# ProximityDetector.net
KiCad netlist of a schematic drawn in Altium Designer
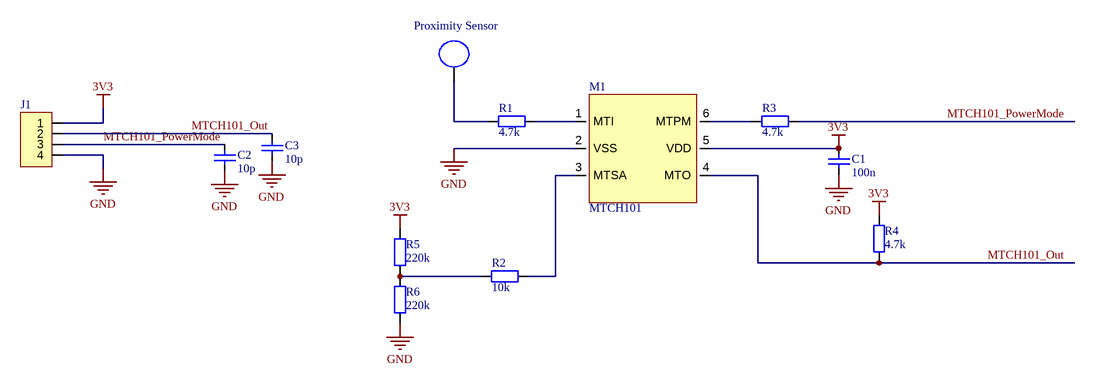
[diagram p0: ProximityDetector.SchDoc]

(export (version "E")
  (design (tool "Eeschema 10.0.6"))
  (components
    (comp (ref "C1")
      (value "100n")
      (footprint "0805_C")
      (description "Cap")
      (libsource (lib "Sch_Lib") (part "Cap"))
    )
    (comp (ref "C2")
      (value "10p")
      (footprint "0805_C")
      (description "Cap")
      (libsource (lib "Sch_Lib") (part "Cap"))
    )
    (comp (ref "C3")
      (value "10p")
      (footprint "0805_C")
      (description "Cap")
      (libsource (lib "Sch_Lib") (part "Cap"))
    )
    (comp (ref "J1") (value "~") (footprint "CON_THT_4P_RM2.54") (libsource (lib "Sch_Lib") (part "CON_4P")))
    (comp (ref "M1")
      (value "MTCH101")
      (footprint "SOT23-6")
      (libsource (lib "ProximityDetector") (part "MTCH101"))
    )
    (comp (ref "Proximity Sensor")
      (value "Detector")
      (footprint "Hole_1.3mm")
      (libsource (lib "ProximityDetector_1") (part "Detector"))
    )
    (comp (ref "R1")
      (value "4.7k")
      (footprint "0805_R")
      (description "Res")
      (libsource (lib "Sch_Lib") (part "Res"))
    )
    (comp (ref "R2")
      (value "10k")
      (footprint "0805_R")
      (description "Res")
      (libsource (lib "Sch_Lib") (part "Res"))
    )
    (comp (ref "R3")
      (value "4.7k")
      (footprint "0805_R")
      (description "Res")
      (libsource (lib "Sch_Lib") (part "Res"))
    )
    (comp (ref "R4")
      (value "4.7k")
      (footprint "0805_R")
      (description "Res")
      (libsource (lib "") (part "Res_1"))
    )
    (comp (ref "R5")
      (value "220k")
      (footprint "0805_R")
      (description "Res")
      (libsource (lib "") (part "Res_1"))
    )
    (comp (ref "R6")
      (value "220k")
      (footprint "0805_R")
      (description "Res")
      (libsource (lib "") (part "Res_1"))
    )
  )
  (nets
    (net (code "1") (name "/MTCH101_Out") (class "Default")
      (node (ref "C3") (pin "2") (pinfunction "2_2") (pintype "passive"))
      (node (ref "J1") (pin "2") (pinfunction "2_2") (pintype "passive"))
      (node (ref "M1") (pin "4") (pinfunction "MTO_4") (pintype "passive"))
      (node (ref "R4") (pin "1") (pinfunction "1_1") (pintype "passive"))
    )
    (net (code "2") (name "/MTCH101_PowerMode") (class "Default")
      (node (ref "C2") (pin "2") (pinfunction "2_2") (pintype "passive"))
      (node (ref "J1") (pin "3") (pinfunction "3_3") (pintype "passive"))
      (node (ref "R3") (pin "2") (pinfunction "2_2") (pintype "passive"))
    )
    (net (code "3") (name "3V3") (class "Default")
      (node (ref "C1") (pin "2") (pinfunction "2_2") (pintype "passive"))
      (node (ref "J1") (pin "1") (pinfunction "1_1") (pintype "passive"))
      (node (ref "M1") (pin "5") (pinfunction "VDD_5") (pintype "passive"))
      (node (ref "R4") (pin "2") (pinfunction "2_2") (pintype "passive"))
      (node (ref "R5") (pin "2") (pinfunction "2_2") (pintype "passive"))
    )
    (net (code "4") (name "GND") (class "Default")
      (node (ref "C1") (pin "1") (pinfunction "1_1") (pintype "passive"))
      (node (ref "C2") (pin "1") (pinfunction "1_1") (pintype "passive"))
      (node (ref "C3") (pin "1") (pinfunction "1_1") (pintype "passive"))
      (node (ref "J1") (pin "4") (pinfunction "4_4") (pintype "passive"))
      (node (ref "M1") (pin "2") (pinfunction "VSS_2") (pintype "passive"))
      (node (ref "R6") (pin "1") (pinfunction "1_1") (pintype "passive"))
    )
    (net (code "5") (name "Net-(M1-MTI)") (class "Default")
      (node (ref "M1") (pin "1") (pinfunction "MTI_1") (pintype "passive"))
      (node (ref "R1") (pin "2") (pinfunction "2_2") (pintype "passive"))
    )
    (net (code "6") (name "Net-(M1-MTPM)") (class "Default")
      (node (ref "M1") (pin "6") (pinfunction "MTPM_6") (pintype "passive"))
      (node (ref "R3") (pin "1") (pinfunction "1_1") (pintype "passive"))
    )
    (net (code "7") (name "Net-(M1-MTSA)") (class "Default")
      (node (ref "M1") (pin "3") (pinfunction "MTSA_3") (pintype "passive"))
      (node (ref "R2") (pin "2") (pinfunction "2_2") (pintype "passive"))
    )
    (net (code "8") (name "Net-(Proximity Sensor-Pad1)") (class "Default")
      (node (ref "Proximity Sensor") (pin "1") (pintype "passive"))
      (node (ref "R1") (pin "1") (pinfunction "1_1") (pintype "passive"))
    )
    (net (code "9") (name "Net-(R2-Pad1)") (class "Default")
      (node (ref "R2") (pin "1") (pinfunction "1_1") (pintype "passive"))
      (node (ref "R5") (pin "1") (pinfunction "1_1") (pintype "passive"))
      (node (ref "R6") (pin "2") (pinfunction "2_2") (pintype "passive"))
    )
  )
)
